# design.net
KiCad netlist of a schematic drawn in EAGLE
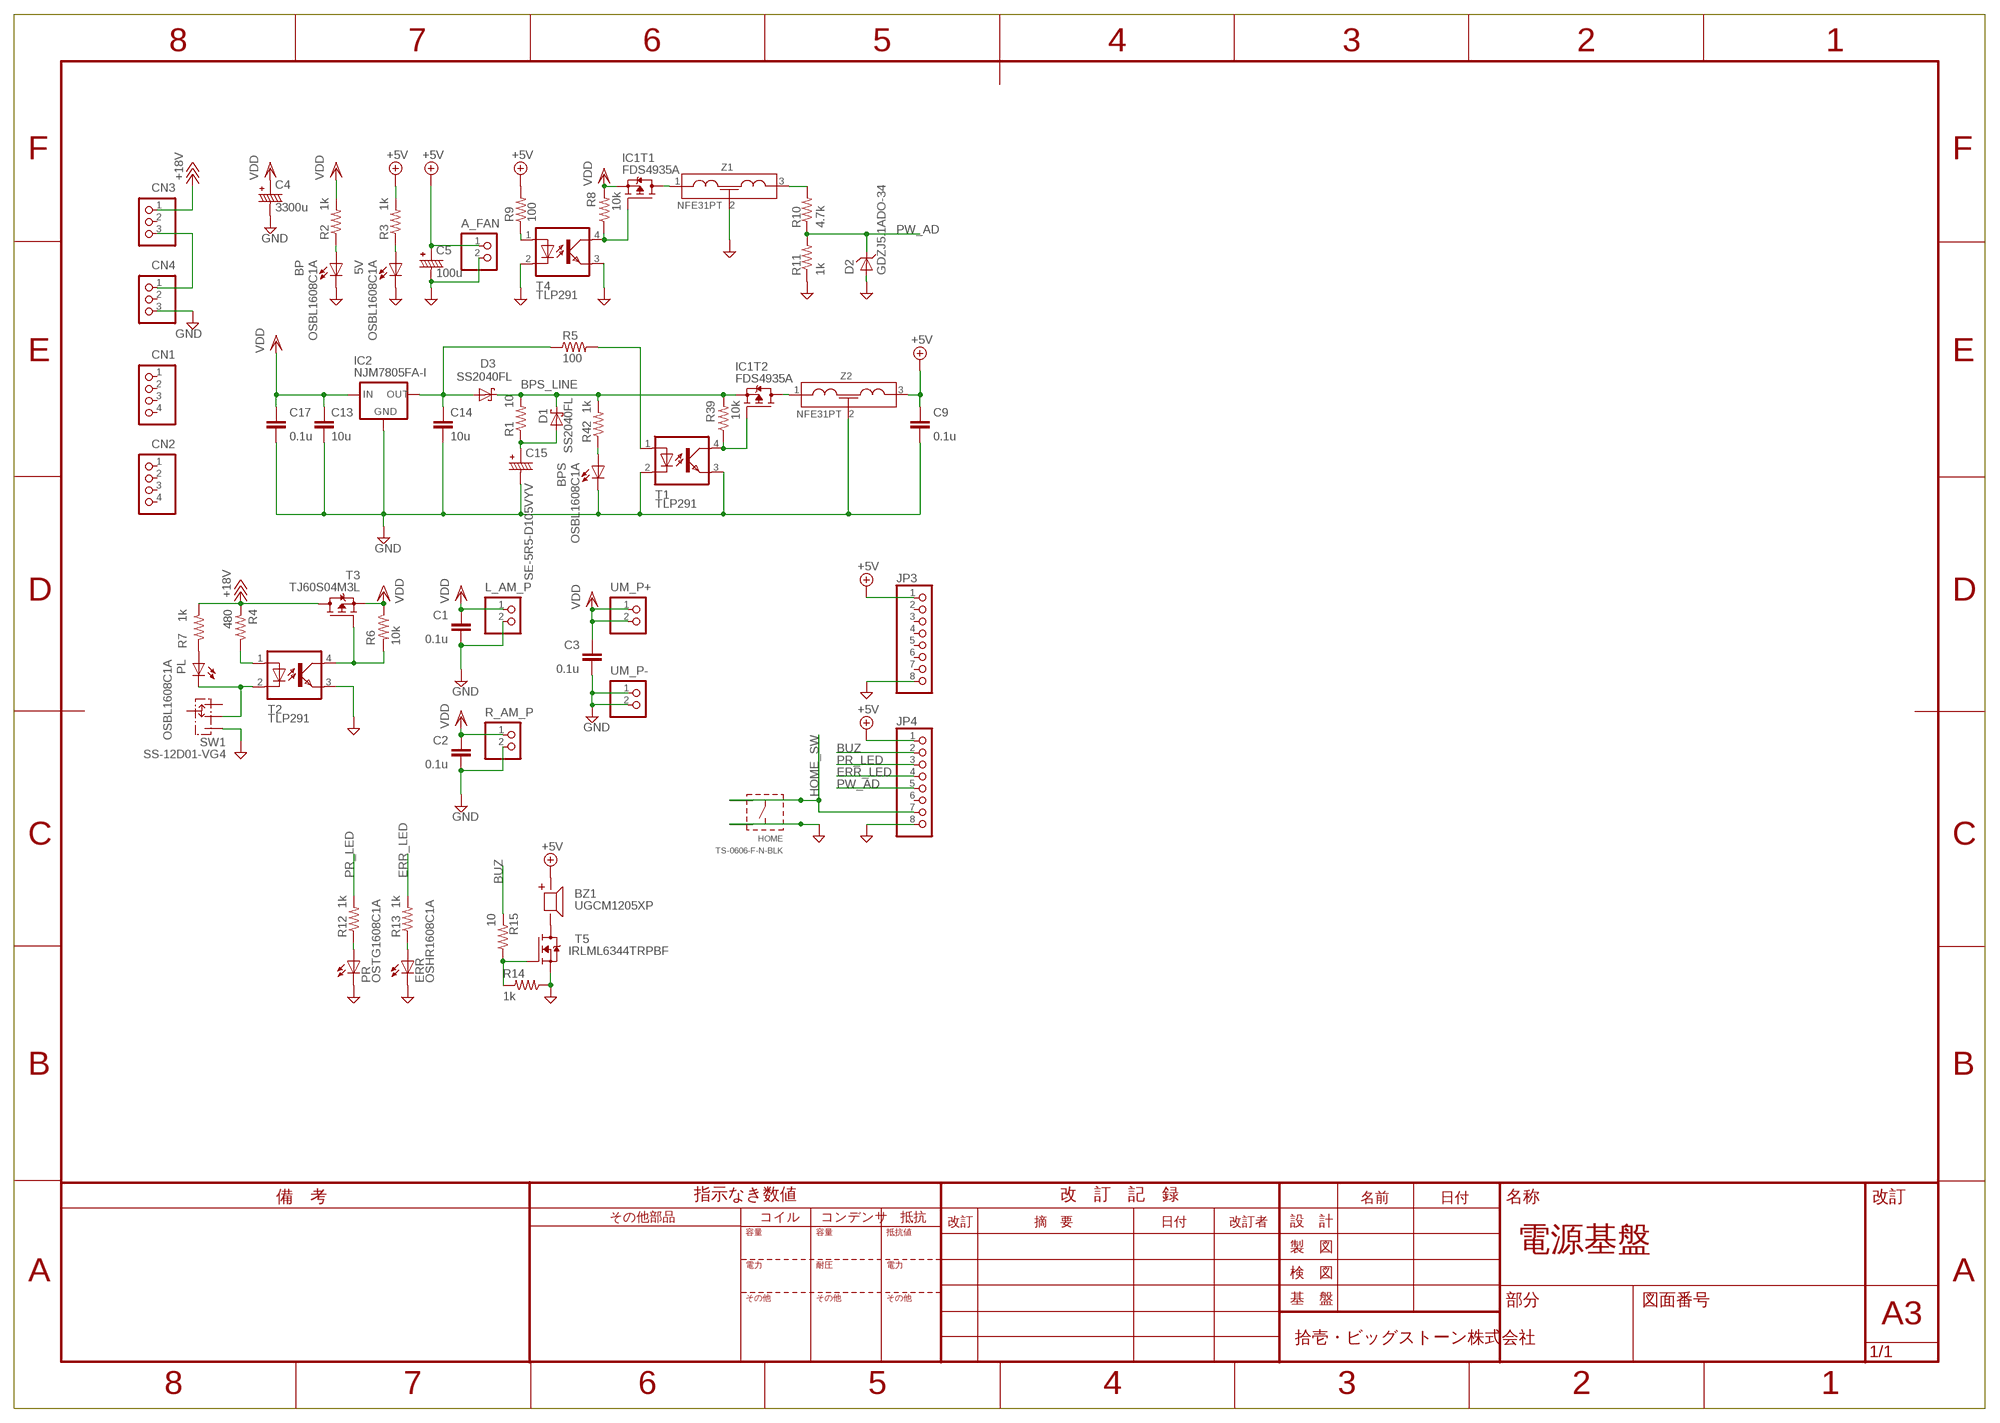
[diagram p0: schematic, sheet 1]

(export (version "E")
  (design (tool "Eeschema 10.0.6"))
  (components
    (comp (ref "5V")
      (value "OSBL1608C1A")
      (footprint "eagle-import:LEDC1608X39N_B")
      (libsource (lib "eagle-import") (part "OSBL1608C1A"))
    )
    (comp (ref "A_FAN")
      (value "B2B-XH-A")
      (footprint "eagle-import:B2B-XH-A")
      (libsource (lib "eagle-import") (part "B2B-XH-A"))
    )
    (comp (ref "BP")
      (value "OSBL1608C1A")
      (footprint "eagle-import:LEDC1608X39N_B")
      (libsource (lib "eagle-import") (part "OSBL1608C1A"))
    )
    (comp (ref "BPS")
      (value "OSBL1608C1A")
      (footprint "eagle-import:LEDC1608X39N_B")
      (libsource (lib "eagle-import") (part "OSBL1608C1A"))
    )
    (comp (ref "BZ1")
      (value "UGCM1205XP")
      (footprint "eagle-import:UGCM1205XP")
      (libsource (lib "eagle-import") (part "UGCM1205XP"))
    )
    (comp (ref "C1")
      (value "0.1u")
      (footprint "eagle-import:C0603")
      (libsource (lib "eagle-import") (part "C-EUC0603"))
    )
    (comp (ref "C2")
      (value "0.1u")
      (footprint "eagle-import:C0603")
      (libsource (lib "eagle-import") (part "C-EUC0603"))
    )
    (comp (ref "C3")
      (value "0.1u")
      (footprint "eagle-import:C0603")
      (libsource (lib "eagle-import") (part "C-EUC0603"))
    )
    (comp (ref "C4")
      (value "3300u")
      (footprint "eagle-import:D18_L25_P7.5_D1")
      (libsource (lib "eagle-import") (part "35WXA3300MEFC18X25"))
    )
    (comp (ref "C5")
      (value "100u")
      (footprint "eagle-import:CPOL6.3-7_2.5")
      (libsource (lib "eagle-import") (part "16MH7100MEFC6.3X7"))
    )
    (comp (ref "C9")
      (value "0.1u")
      (footprint "eagle-import:C0603")
      (libsource (lib "eagle-import") (part "C-EUC0603"))
    )
    (comp (ref "C13")
      (value "10u")
      (footprint "eagle-import:C0805")
      (libsource (lib "eagle-import") (part "C2012"))
    )
    (comp (ref "C14")
      (value "10u")
      (footprint "eagle-import:C0805")
      (libsource (lib "eagle-import") (part "C2012"))
    )
    (comp (ref "C15")
      (value "SE-5R5-D105VYV")
      (footprint "eagle-import:SE-5R5-D105VYV")
      (libsource (lib "eagle-import") (part "SE-5R5-D105VYV"))
    )
    (comp (ref "C17")
      (value "0.1u")
      (footprint "eagle-import:C0603")
      (libsource (lib "eagle-import") (part "C-EUC0603"))
    )
    (comp (ref "CN1")
      (value "B4B-XH-A")
      (footprint "eagle-import:B4B-XH-A")
      (libsource (lib "eagle-import") (part "B4B-XH-A"))
    )
    (comp (ref "CN2")
      (value "B4B-XH-A")
      (footprint "eagle-import:B4B-XH-A")
      (libsource (lib "eagle-import") (part "B4B-XH-A"))
    )
    (comp (ref "CN3")
      (value "B3P-VH")
      (footprint "eagle-import:B3P-VH")
      (libsource (lib "eagle-import") (part "B3P-VH"))
    )
    (comp (ref "CN4")
      (value "B3P-VH")
      (footprint "eagle-import:B3P-VH")
      (libsource (lib "eagle-import") (part "B3P-VH"))
    )
    (comp (ref "D1")
      (value "SS2040FL")
      (footprint "eagle-import:SOD-123")
      (libsource (lib "eagle-import") (part "SS2040FL"))
    )
    (comp (ref "D2")
      (value "GDZJ5.1ADO-34")
      (footprint "eagle-import:DIOAD590W50L290D210B")
      (libsource (lib "eagle-import") (part "GDZJ5.1ADO-34"))
    )
    (comp (ref "D3")
      (value "SS2040FL")
      (footprint "eagle-import:SOD-123")
      (libsource (lib "eagle-import") (part "SS2040FL"))
    )
    (comp (ref "ERR")
      (value "OSHR1608C1A")
      (footprint "eagle-import:LEDC1608X39N_R")
      (libsource (lib "eagle-import") (part "OSHR1608C1A"))
    )
    (comp (ref "HOME")
      (value "TS-0606-F-N-BLK")
      (footprint "eagle-import:TS-0606-F-N")
      (libsource (lib "eagle-import") (part "TS-0606-F-N-BLK"))
    )
    (comp (ref "IC1")
      (value "FDS4935A")
      (footprint "eagle-import:SOIC127P600X250-8N")
      (libsource (lib "eagle-import") (part "FDS4935A"))
    )
    (comp (ref "IC2")
      (value "NJM7805FA-I")
      (footprint "eagle-import:TO220")
      (libsource (lib "eagle-import") (part "NJM7805FA-I"))
    )
    (comp (ref "JP3")
      (value "PINHD-1X8")
      (footprint "eagle-import:1X08")
      (libsource (lib "eagle-import") (part "PINHD-1X8"))
    )
    (comp (ref "JP4")
      (value "PINHD-1X8")
      (footprint "eagle-import:1X08")
      (libsource (lib "eagle-import") (part "PINHD-1X8"))
    )
    (comp (ref "L_AM_P")
      (value "B2P-VH")
      (footprint "eagle-import:B2P-VH")
      (libsource (lib "eagle-import") (part "B2P-VH"))
    )
    (comp (ref "PL")
      (value "OSBL1608C1A")
      (footprint "eagle-import:LEDC1608X39N_B")
      (libsource (lib "eagle-import") (part "OSBL1608C1A"))
    )
    (comp (ref "PR")
      (value "OSTG1608C1A")
      (footprint "eagle-import:LEDC1608X39N_G")
      (libsource (lib "eagle-import") (part "OSTG1608C1A"))
    )
    (comp (ref "R1")
      (value "10")
      (footprint "eagle-import:R0603")
      (libsource (lib "eagle-import") (part "R-US_R0603"))
    )
    (comp (ref "R2")
      (value "1k")
      (footprint "eagle-import:R0603")
      (libsource (lib "eagle-import") (part "R-US_R0603"))
    )
    (comp (ref "R3")
      (value "1k")
      (footprint "eagle-import:R0603")
      (libsource (lib "eagle-import") (part "R-US_R0603"))
    )
    (comp (ref "R4")
      (value "480")
      (footprint "eagle-import:R0603")
      (libsource (lib "eagle-import") (part "R-US_R0603"))
    )
    (comp (ref "R5")
      (value "100")
      (footprint "eagle-import:R0603")
      (libsource (lib "eagle-import") (part "R-US_R0603"))
    )
    (comp (ref "R6")
      (value "10k")
      (footprint "eagle-import:R0603")
      (libsource (lib "eagle-import") (part "R-US_R0603"))
    )
    (comp (ref "R7")
      (value "1k")
      (footprint "eagle-import:R0603")
      (libsource (lib "eagle-import") (part "R-US_R0603"))
    )
    (comp (ref "R8")
      (value "10k")
      (footprint "eagle-import:R0603")
      (libsource (lib "eagle-import") (part "R-US_R0603"))
    )
    (comp (ref "R9")
      (value "100")
      (footprint "eagle-import:R0603")
      (libsource (lib "eagle-import") (part "R-US_R0603"))
    )
    (comp (ref "R10")
      (value "4.7k")
      (footprint "eagle-import:R0603")
      (libsource (lib "eagle-import") (part "R-US_R0603"))
    )
    (comp (ref "R11")
      (value "1k")
      (footprint "eagle-import:R0603")
      (libsource (lib "eagle-import") (part "R-US_R0603"))
    )
    (comp (ref "R12")
      (value "1k")
      (footprint "eagle-import:R0603")
      (libsource (lib "eagle-import") (part "R-US_R0603"))
    )
    (comp (ref "R13")
      (value "1k")
      (footprint "eagle-import:R0603")
      (libsource (lib "eagle-import") (part "R-US_R0603"))
    )
    (comp (ref "R14")
      (value "1k")
      (footprint "eagle-import:R0603")
      (libsource (lib "eagle-import") (part "R-US_R0603"))
    )
    (comp (ref "R15")
      (value "10")
      (footprint "eagle-import:R0603")
      (libsource (lib "eagle-import") (part "R-US_R0603"))
    )
    (comp (ref "R39")
      (value "10k")
      (footprint "eagle-import:R0603")
      (libsource (lib "eagle-import") (part "R-US_R0603"))
    )
    (comp (ref "R42")
      (value "1k")
      (footprint "eagle-import:R0603")
      (libsource (lib "eagle-import") (part "R-US_R0603"))
    )
    (comp (ref "R_AM_P")
      (value "B2P-VH")
      (footprint "eagle-import:B2P-VH")
      (libsource (lib "eagle-import") (part "B2P-VH"))
    )
    (comp (ref "SW1")
      (value "SS-12D01-VG4")
      (footprint "eagle-import:SS-12D01-VG4")
      (libsource (lib "eagle-import") (part "SS-12D01-VG4"))
    )
    (comp (ref "T1")
      (value "TLP291")
      (footprint "eagle-import:SOIC127P700X210-4N")
      (libsource (lib "eagle-import") (part "TLP291"))
    )
    (comp (ref "T2")
      (value "TLP291")
      (footprint "eagle-import:SOIC127P700X210-4N")
      (libsource (lib "eagle-import") (part "TLP291"))
    )
    (comp (ref "T3")
      (value "TJ60S04M3L")
      (footprint "eagle-import:DPACK")
      (libsource (lib "eagle-import") (part "TJ60S04M3L"))
    )
    (comp (ref "T4")
      (value "TLP291")
      (footprint "eagle-import:SOIC127P700X210-4N")
      (libsource (lib "eagle-import") (part "TLP291"))
    )
    (comp (ref "T5")
      (value "IRLML6344TRPBF")
      (footprint "eagle-import:SOT95P240X110-3N")
      (libsource (lib "eagle-import") (part "IRLML6344TRPBF"))
    )
    (comp (ref "UM_P+")
      (value "B2P-VH")
      (footprint "eagle-import:B2P-VH")
      (libsource (lib "eagle-import") (part "B2P-VH"))
    )
    (comp (ref "UM_P-")
      (value "B2P-VH")
      (footprint "eagle-import:B2P-VH")
      (libsource (lib "eagle-import") (part "B2P-VH"))
    )
    (comp (ref "Z1")
      (value "NFE31PT")
      (footprint "eagle-import:NFE31")
      (libsource (lib "eagle-import") (part "NFE31PT"))
    )
    (comp (ref "Z2")
      (value "NFE31PT")
      (footprint "eagle-import:NFE31")
      (libsource (lib "eagle-import") (part "NFE31PT"))
    )
  )
  (nets
    (net (code "1") (name "+5V") (class "Default")
      (node (ref "A_FAN") (pin "1") (pinfunction "1_1") (pintype "passive"))
      (node (ref "BZ1") (pin "+") (pinfunction "P$1_+") (pintype "bidirectional"))
      (node (ref "C5") (pin "+") (pinfunction "+_+") (pintype "passive"))
      (node (ref "C9") (pin "1") (pinfunction "1_1") (pintype "passive"))
      (node (ref "JP3") (pin "1") (pinfunction "1_1") (pintype "passive"))
      (node (ref "JP4") (pin "1") (pinfunction "1_1") (pintype "passive"))
      (node (ref "R3") (pin "2") (pinfunction "2_2") (pintype "passive"))
      (node (ref "R9") (pin "2") (pinfunction "2_2") (pintype "passive"))
      (node (ref "Z2") (pin "3") (pinfunction "3_3") (pintype "passive"))
    )
    (net (code "2") (name "+18V") (class "Default")
      (node (ref "CN3") (pin "1") (pinfunction "1_1") (pintype "passive"))
      (node (ref "R4") (pin "2") (pinfunction "2_2") (pintype "passive"))
      (node (ref "R7") (pin "2") (pinfunction "2_2") (pintype "passive"))
      (node (ref "T3") (pin "2") (pinfunction "D_2") (pintype "passive"))
    )
    (net (code "3") (name "/BPS_LINE") (class "Default")
      (node (ref "D1") (pin "1") (pinfunction "C_1") (pintype "passive"))
      (node (ref "D3") (pin "1") (pinfunction "C_1") (pintype "passive"))
      (node (ref "IC1") (pin "1") (pinfunction "S_1") (pintype "passive"))
      (node (ref "R1") (pin "2") (pinfunction "2_2") (pintype "passive"))
      (node (ref "R39") (pin "2") (pinfunction "2_2") (pintype "passive"))
      (node (ref "R42") (pin "2") (pinfunction "2_2") (pintype "passive"))
    )
    (net (code "4") (name "/BUZ") (class "Default")
      (node (ref "JP4") (pin "2") (pinfunction "2_2") (pintype "passive"))
      (node (ref "R15") (pin "2") (pinfunction "2_2") (pintype "passive"))
    )
    (net (code "5") (name "/ERR_LED") (class "Default")
      (node (ref "JP4") (pin "3") (pinfunction "3_3") (pintype "passive"))
      (node (ref "R13") (pin "2") (pinfunction "2_2") (pintype "passive"))
    )
    (net (code "6") (name "/HOME_SW") (class "Default")
      (node (ref "HOME") (pin "T1") (pinfunction "T1_T1") (pintype "bidirectional"))
      (node (ref "HOME") (pin "T2") (pinfunction "T2_T2") (pintype "bidirectional"))
      (node (ref "JP4") (pin "7") (pinfunction "7_7") (pintype "passive"))
    )
    (net (code "7") (name "/PR_LED") (class "Default")
      (node (ref "JP4") (pin "4") (pinfunction "4_4") (pintype "passive"))
      (node (ref "R12") (pin "2") (pinfunction "2_2") (pintype "passive"))
    )
    (net (code "8") (name "/PW_AD") (class "Default")
      (node (ref "D2") (pin "1") (pinfunction "C_1") (pintype "passive"))
      (node (ref "JP4") (pin "5") (pinfunction "5_5") (pintype "passive"))
      (node (ref "R10") (pin "1") (pinfunction "1_1") (pintype "passive"))
      (node (ref "R11") (pin "2") (pinfunction "2_2") (pintype "passive"))
    )
    (net (code "9") (name "GND") (class "Default")
      (node (ref "5V") (pin "2") (pinfunction "C_2") (pintype "passive"))
      (node (ref "A_FAN") (pin "2") (pinfunction "2_2") (pintype "passive"))
      (node (ref "BP") (pin "2") (pinfunction "C_2") (pintype "passive"))
      (node (ref "BPS") (pin "2") (pinfunction "C_2") (pintype "passive"))
      (node (ref "C1") (pin "2") (pinfunction "2_2") (pintype "passive"))
      (node (ref "C13") (pin "2") (pinfunction "2_2") (pintype "passive"))
      (node (ref "C14") (pin "2") (pinfunction "2_2") (pintype "passive"))
      (node (ref "C15") (pin "-") (pinfunction "-_-") (pintype "passive"))
      (node (ref "C17") (pin "2") (pinfunction "2_2") (pintype "passive"))
      (node (ref "C2") (pin "2") (pinfunction "2_2") (pintype "passive"))
      (node (ref "C3") (pin "2") (pinfunction "2_2") (pintype "passive"))
      (node (ref "C4") (pin "-") (pinfunction "-_-") (pintype "passive"))
      (node (ref "C5") (pin "-") (pinfunction "-_-") (pintype "passive"))
      (node (ref "C9") (pin "2") (pinfunction "2_2") (pintype "passive"))
      (node (ref "CN4") (pin "3") (pinfunction "3_3") (pintype "passive"))
      (node (ref "D2") (pin "2") (pinfunction "A_2") (pintype "passive"))
      (node (ref "ERR") (pin "2") (pinfunction "C_2") (pintype "passive"))
      (node (ref "HOME") (pin "T3") (pinfunction "T3_T3") (pintype "bidirectional"))
      (node (ref "HOME") (pin "T4") (pinfunction "T4_T4") (pintype "bidirectional"))
      (node (ref "IC2") (pin "2") (pinfunction "GND_2") (pintype "input"))
      (node (ref "JP3") (pin "8") (pinfunction "8_8") (pintype "passive"))
      (node (ref "JP4") (pin "8") (pinfunction "8_8") (pintype "passive"))
      (node (ref "L_AM_P") (pin "2") (pinfunction "2_2") (pintype "passive"))
      (node (ref "PR") (pin "K") (pinfunction "C_K") (pintype "passive"))
      (node (ref "R11") (pin "1") (pinfunction "1_1") (pintype "passive"))
      (node (ref "R14") (pin "1") (pinfunction "1_1") (pintype "passive"))
      (node (ref "R_AM_P") (pin "2") (pinfunction "2_2") (pintype "passive"))
      (node (ref "SW1") (pin "NO") (pinfunction "NO_NO") (pintype "bidirectional"))
      (node (ref "T1") (pin "2") (pinfunction "C_2") (pintype "passive"))
      (node (ref "T1") (pin "3") (pinfunction "EMIT_3") (pintype "passive"))
      (node (ref "T2") (pin "3") (pinfunction "EMIT_3") (pintype "passive"))
      (node (ref "T4") (pin "2") (pinfunction "C_2") (pintype "passive"))
      (node (ref "T4") (pin "3") (pinfunction "EMIT_3") (pintype "passive"))
      (node (ref "T5") (pin "2") (pinfunction "S_2") (pintype "passive"))
      (node (ref "UM_P-") (pin "1") (pinfunction "1_1") (pintype "passive"))
      (node (ref "UM_P-") (pin "2") (pinfunction "2_2") (pintype "passive"))
      (node (ref "Z1") (pin "2") (pinfunction "2_2") (pintype "passive"))
      (node (ref "Z2") (pin "2") (pinfunction "2_2") (pintype "passive"))
    )
    (net (code "10") (name "Net-(5V-A)") (class "Default")
      (node (ref "5V") (pin "1") (pinfunction "A_1") (pintype "passive"))
      (node (ref "R3") (pin "1") (pinfunction "1_1") (pintype "passive"))
    )
    (net (code "11") (name "Net-(BP-A)") (class "Default")
      (node (ref "BP") (pin "1") (pinfunction "A_1") (pintype "passive"))
      (node (ref "R2") (pin "1") (pinfunction "1_1") (pintype "passive"))
    )
    (net (code "12") (name "Net-(BPS-A)") (class "Default")
      (node (ref "BPS") (pin "1") (pinfunction "A_1") (pintype "passive"))
      (node (ref "R42") (pin "1") (pinfunction "1_1") (pintype "passive"))
    )
    (net (code "13") (name "Net-(BZ1-P$2)") (class "Default")
      (node (ref "BZ1") (pin "-") (pinfunction "P$2_-") (pintype "bidirectional"))
      (node (ref "T5") (pin "3") (pinfunction "D_3") (pintype "passive"))
    )
    (net (code "14") (name "Net-(CN3-Pad3)") (class "Default")
      (node (ref "CN3") (pin "3") (pinfunction "3_3") (pintype "passive"))
      (node (ref "CN4") (pin "1") (pinfunction "1_1") (pintype "passive"))
    )
    (net (code "15") (name "Net-(D1-A)") (class "Default")
      (node (ref "C15") (pin "+") (pinfunction "+_+") (pintype "passive"))
      (node (ref "D1") (pin "2") (pinfunction "A_2") (pintype "passive"))
      (node (ref "R1") (pin "1") (pinfunction "1_1") (pintype "passive"))
    )
    (net (code "16") (name "Net-(D3-A)") (class "Default")
      (node (ref "C14") (pin "1") (pinfunction "1_1") (pintype "passive"))
      (node (ref "D3") (pin "2") (pinfunction "A_2") (pintype "passive"))
      (node (ref "IC2") (pin "3") (pinfunction "OUT_3") (pintype "passive"))
      (node (ref "R5") (pin "1") (pinfunction "1_1") (pintype "passive"))
    )
    (net (code "17") (name "Net-(ERR-A)") (class "Default")
      (node (ref "ERR") (pin "1") (pinfunction "A_1") (pintype "passive"))
      (node (ref "R13") (pin "1") (pinfunction "1_1") (pintype "passive"))
    )
    (net (code "18") (name "Net-(IC1A-D-Pad5)") (class "Default")
      (node (ref "IC1") (pin "5") (pinfunction "D_5") (pintype "passive"))
      (node (ref "IC1") (pin "6") (pinfunction "D_6") (pintype "passive"))
      (node (ref "Z1") (pin "1") (pinfunction "1_1") (pintype "passive"))
    )
    (net (code "19") (name "Net-(IC1A-G)") (class "Default")
      (node (ref "IC1") (pin "4") (pinfunction "G_4") (pintype "passive"))
      (node (ref "R8") (pin "1") (pinfunction "1_1") (pintype "passive"))
      (node (ref "T4") (pin "4") (pinfunction "COL_4") (pintype "passive"))
    )
    (net (code "20") (name "Net-(IC1B-D-Pad7)") (class "Default")
      (node (ref "IC1") (pin "7") (pinfunction "D_7") (pintype "passive"))
      (node (ref "IC1") (pin "8") (pinfunction "D_8") (pintype "passive"))
      (node (ref "Z2") (pin "1") (pinfunction "1_1") (pintype "passive"))
    )
    (net (code "21") (name "Net-(IC1B-G)") (class "Default")
      (node (ref "IC1") (pin "2") (pinfunction "G_2") (pintype "passive"))
      (node (ref "R39") (pin "1") (pinfunction "1_1") (pintype "passive"))
      (node (ref "T1") (pin "4") (pinfunction "COL_4") (pintype "passive"))
    )
    (net (code "22") (name "Net-(PL-A)") (class "Default")
      (node (ref "PL") (pin "1") (pinfunction "A_1") (pintype "passive"))
      (node (ref "R7") (pin "1") (pinfunction "1_1") (pintype "passive"))
    )
    (net (code "23") (name "Net-(PL-C)") (class "Default")
      (node (ref "PL") (pin "2") (pinfunction "C_2") (pintype "passive"))
      (node (ref "SW1") (pin "COM") (pinfunction "COM_COM") (pintype "bidirectional"))
      (node (ref "T2") (pin "2") (pinfunction "C_2") (pintype "passive"))
    )
    (net (code "24") (name "Net-(PR-PadA)") (class "Default")
      (node (ref "PR") (pin "A") (pinfunction "A_A") (pintype "passive"))
      (node (ref "R12") (pin "1") (pinfunction "1_1") (pintype "passive"))
    )
    (net (code "25") (name "Net-(R10-Pad2)") (class "Default")
      (node (ref "R10") (pin "2") (pinfunction "2_2") (pintype "passive"))
      (node (ref "Z1") (pin "3") (pinfunction "3_3") (pintype "passive"))
    )
    (net (code "26") (name "Net-(T1-A)") (class "Default")
      (node (ref "R5") (pin "2") (pinfunction "2_2") (pintype "passive"))
      (node (ref "T1") (pin "1") (pinfunction "A_1") (pintype "passive"))
    )
    (net (code "27") (name "Net-(T2-A)") (class "Default")
      (node (ref "R4") (pin "1") (pinfunction "1_1") (pintype "passive"))
      (node (ref "T2") (pin "1") (pinfunction "A_1") (pintype "passive"))
    )
    (net (code "28") (name "Net-(T2-COL)") (class "Default")
      (node (ref "R6") (pin "2") (pinfunction "2_2") (pintype "passive"))
      (node (ref "T2") (pin "4") (pinfunction "COL_4") (pintype "passive"))
      (node (ref "T3") (pin "1") (pinfunction "G_1") (pintype "passive"))
    )
    (net (code "29") (name "Net-(T4-A)") (class "Default")
      (node (ref "R9") (pin "1") (pinfunction "1_1") (pintype "passive"))
      (node (ref "T4") (pin "1") (pinfunction "A_1") (pintype "passive"))
    )
    (net (code "30") (name "Net-(T5-G)") (class "Default")
      (node (ref "R14") (pin "2") (pinfunction "2_2") (pintype "passive"))
      (node (ref "R15") (pin "1") (pinfunction "1_1") (pintype "passive"))
      (node (ref "T5") (pin "1") (pinfunction "G_1") (pintype "passive"))
    )
    (net (code "31") (name "VDD") (class "Default")
      (node (ref "C1") (pin "1") (pinfunction "1_1") (pintype "passive"))
      (node (ref "C13") (pin "1") (pinfunction "1_1") (pintype "passive"))
      (node (ref "C17") (pin "1") (pinfunction "1_1") (pintype "passive"))
      (node (ref "C2") (pin "1") (pinfunction "1_1") (pintype "passive"))
      (node (ref "C3") (pin "1") (pinfunction "1_1") (pintype "passive"))
      (node (ref "C4") (pin "+") (pinfunction "+_+") (pintype "passive"))
      (node (ref "IC1") (pin "3") (pinfunction "S_3") (pintype "passive"))
      (node (ref "IC2") (pin "1") (pinfunction "IN_1") (pintype "input"))
      (node (ref "L_AM_P") (pin "1") (pinfunction "1_1") (pintype "passive"))
      (node (ref "R2") (pin "2") (pinfunction "2_2") (pintype "passive"))
      (node (ref "R6") (pin "1") (pinfunction "1_1") (pintype "passive"))
      (node (ref "R8") (pin "2") (pinfunction "2_2") (pintype "passive"))
      (node (ref "R_AM_P") (pin "1") (pinfunction "1_1") (pintype "passive"))
      (node (ref "T3") (pin "3") (pinfunction "S_3") (pintype "passive"))
      (node (ref "UM_P+") (pin "1") (pinfunction "1_1") (pintype "passive"))
      (node (ref "UM_P+") (pin "2") (pinfunction "2_2") (pintype "passive"))
    )
    (net (code "32") (name "unconnected-(CN1-Pad1)") (class "Default")
      (node (ref "CN1") (pin "1") (pinfunction "1_1") (pintype "passive"))
    )
    (net (code "33") (name "unconnected-(CN1-Pad2)") (class "Default")
      (node (ref "CN1") (pin "2") (pinfunction "2_2") (pintype "passive"))
    )
    (net (code "34") (name "unconnected-(CN1-Pad3)") (class "Default")
      (node (ref "CN1") (pin "3") (pinfunction "3_3") (pintype "passive"))
    )
    (net (code "35") (name "unconnected-(CN1-Pad4)") (class "Default")
      (node (ref "CN1") (pin "4") (pinfunction "4_4") (pintype "passive"))
    )
    (net (code "36") (name "unconnected-(CN2-Pad1)") (class "Default")
      (node (ref "CN2") (pin "1") (pinfunction "1_1") (pintype "passive"))
    )
    (net (code "37") (name "unconnected-(CN2-Pad2)") (class "Default")
      (node (ref "CN2") (pin "2") (pinfunction "2_2") (pintype "passive"))
    )
    (net (code "38") (name "unconnected-(CN2-Pad3)") (class "Default")
      (node (ref "CN2") (pin "3") (pinfunction "3_3") (pintype "passive"))
    )
    (net (code "39") (name "unconnected-(CN2-Pad4)") (class "Default")
      (node (ref "CN2") (pin "4") (pinfunction "4_4") (pintype "passive"))
    )
    (net (code "40") (name "unconnected-(CN3-Pad2)") (class "Default")
      (node (ref "CN3") (pin "2") (pinfunction "2_2") (pintype "passive"))
    )
    (net (code "41") (name "unconnected-(CN4-Pad2)") (class "Default")
      (node (ref "CN4") (pin "2") (pinfunction "2_2") (pintype "passive"))
    )
    (net (code "42") (name "unconnected-(JP3-Pad2)") (class "Default")
      (node (ref "JP3") (pin "2") (pinfunction "2_2") (pintype "passive"))
    )
    (net (code "43") (name "unconnected-(JP3-Pad3)") (class "Default")
      (node (ref "JP3") (pin "3") (pinfunction "3_3") (pintype "passive"))
    )
    (net (code "44") (name "unconnected-(JP3-Pad4)") (class "Default")
      (node (ref "JP3") (pin "4") (pinfunction "4_4") (pintype "passive"))
    )
    (net (code "45") (name "unconnected-(JP3-Pad5)") (class "Default")
      (node (ref "JP3") (pin "5") (pinfunction "5_5") (pintype "passive"))
    )
    (net (code "46") (name "unconnected-(JP3-Pad6)") (class "Default")
      (node (ref "JP3") (pin "6") (pinfunction "6_6") (pintype "passive"))
    )
    (net (code "47") (name "unconnected-(JP3-Pad7)") (class "Default")
      (node (ref "JP3") (pin "7") (pinfunction "7_7") (pintype "passive"))
    )
    (net (code "48") (name "unconnected-(JP4-Pad6)") (class "Default")
      (node (ref "JP4") (pin "6") (pinfunction "6_6") (pintype "passive"))
    )
    (net (code "49") (name "unconnected-(SW1-PadNC)") (class "Default")
      (node (ref "SW1") (pin "NC") (pinfunction "NC_NC") (pintype "bidirectional"))
    )
  )
)
